# Backplane3_0.net
KiCad netlist of a schematic drawn in Altium Designer
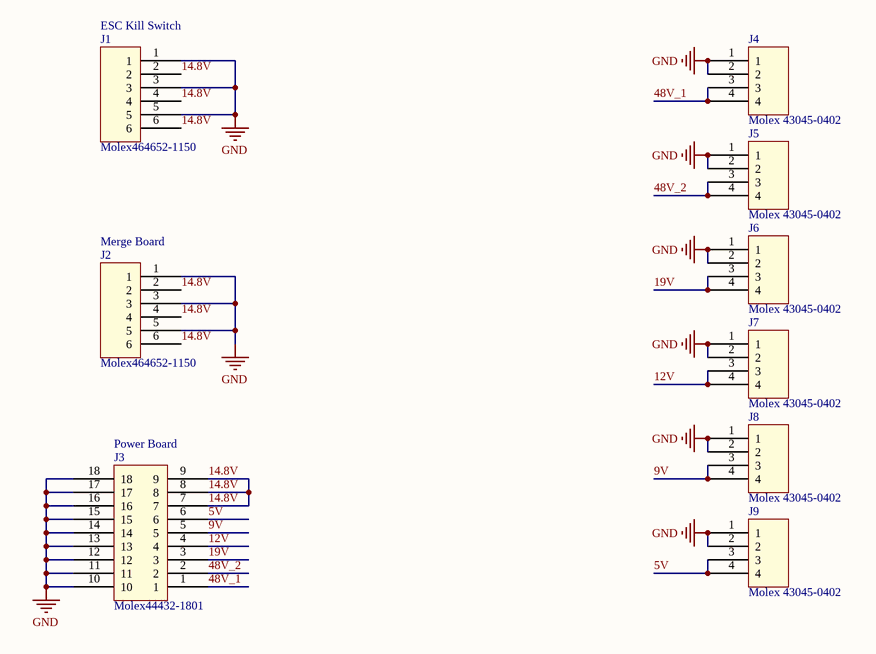
[diagram p0: Backplane3_0.SchDoc]

(export (version "E")
  (design (tool "Eeschema 10.0.6"))
  (components
    (comp (ref "J1")
      (value "Molex464652-1150")
      (footprint "PCBComponent_1")
      (libsource (lib "Molex46562-1150") (part "Molex46562-1150"))
    )
    (comp (ref "J2")
      (value "Molex464652-1150")
      (footprint "PCBComponent_1")
      (libsource (lib "Molex46562-1150") (part "Molex46562-1150"))
    )
    (comp (ref "J3")
      (value "Molex44432-1801")
      (footprint "Molex44432-1801")
      (libsource (lib "Molex44432-1801") (part "Molex44432-1801"))
    )
    (comp (ref "J4")
      (value "Molex 43045-0402")
      (footprint "Molex43045-0402")
      (libsource (lib "Molex43045-0402") (part "Molex43045-0402"))
    )
    (comp (ref "J5")
      (value "Molex 43045-0402")
      (footprint "Molex43045-0402")
      (libsource (lib "Molex43045-0402") (part "Molex43045-0402"))
    )
    (comp (ref "J6")
      (value "Molex 43045-0402")
      (footprint "Molex43045-0402")
      (libsource (lib "Molex43045-0402") (part "Molex43045-0402"))
    )
    (comp (ref "J7")
      (value "Molex 43045-0402")
      (footprint "Molex43045-0402")
      (libsource (lib "Molex43045-0402") (part "Molex43045-0402"))
    )
    (comp (ref "J8")
      (value "Molex 43045-0402")
      (footprint "Molex43045-0402")
      (libsource (lib "Molex43045-0402") (part "Molex43045-0402"))
    )
    (comp (ref "J9")
      (value "Molex 43045-0402")
      (footprint "Molex43045-0402")
      (libsource (lib "Molex43045-0402") (part "Molex43045-0402"))
    )
  )
  (nets
    (net (code "1") (name "/5V") (class "Default")
      (node (ref "J3") (pin "6") (pinfunction "6_6") (pintype "passive"))
      (node (ref "J9") (pin "3") (pinfunction "3_3") (pintype "passive"))
      (node (ref "J9") (pin "4") (pinfunction "4_4") (pintype "passive"))
    )
    (net (code "2") (name "/9V") (class "Default")
      (node (ref "J3") (pin "5") (pinfunction "5_5") (pintype "passive"))
      (node (ref "J8") (pin "3") (pinfunction "3_3") (pintype "passive"))
      (node (ref "J8") (pin "4") (pinfunction "4_4") (pintype "passive"))
    )
    (net (code "3") (name "/12V") (class "Default")
      (node (ref "J3") (pin "4") (pinfunction "4_4") (pintype "passive"))
      (node (ref "J7") (pin "3") (pinfunction "3_3") (pintype "passive"))
      (node (ref "J7") (pin "4") (pinfunction "4_4") (pintype "passive"))
    )
    (net (code "4") (name "/14.8V") (class "Default")
      (node (ref "J1") (pin "2") (pinfunction "2_2") (pintype "passive"))
      (node (ref "J1") (pin "4") (pinfunction "4_4") (pintype "passive"))
      (node (ref "J1") (pin "6") (pinfunction "6_6") (pintype "passive"))
      (node (ref "J2") (pin "2") (pinfunction "2_2") (pintype "passive"))
      (node (ref "J2") (pin "4") (pinfunction "4_4") (pintype "passive"))
      (node (ref "J2") (pin "6") (pinfunction "6_6") (pintype "passive"))
      (node (ref "J3") (pin "7") (pinfunction "7_7") (pintype "passive"))
      (node (ref "J3") (pin "8") (pinfunction "8_8") (pintype "passive"))
      (node (ref "J3") (pin "9") (pinfunction "9_9") (pintype "passive"))
    )
    (net (code "5") (name "/19V") (class "Default")
      (node (ref "J3") (pin "3") (pinfunction "3_3") (pintype "passive"))
      (node (ref "J6") (pin "3") (pinfunction "3_3") (pintype "passive"))
      (node (ref "J6") (pin "4") (pinfunction "4_4") (pintype "passive"))
    )
    (net (code "6") (name "/48V_1") (class "Default")
      (node (ref "J3") (pin "1") (pinfunction "1_1") (pintype "passive"))
      (node (ref "J4") (pin "3") (pinfunction "3_3") (pintype "passive"))
      (node (ref "J4") (pin "4") (pinfunction "4_4") (pintype "passive"))
    )
    (net (code "7") (name "/48V_2") (class "Default")
      (node (ref "J3") (pin "2") (pinfunction "2_2") (pintype "passive"))
      (node (ref "J5") (pin "3") (pinfunction "3_3") (pintype "passive"))
      (node (ref "J5") (pin "4") (pinfunction "4_4") (pintype "passive"))
    )
    (net (code "8") (name "GND") (class "Default")
      (node (ref "J1") (pin "1") (pinfunction "1_1") (pintype "passive"))
      (node (ref "J1") (pin "3") (pinfunction "3_3") (pintype "passive"))
      (node (ref "J1") (pin "5") (pinfunction "5_5") (pintype "passive"))
      (node (ref "J2") (pin "1") (pinfunction "1_1") (pintype "passive"))
      (node (ref "J2") (pin "3") (pinfunction "3_3") (pintype "passive"))
      (node (ref "J2") (pin "5") (pinfunction "5_5") (pintype "passive"))
      (node (ref "J3") (pin "10") (pinfunction "10_10") (pintype "passive"))
      (node (ref "J3") (pin "11") (pinfunction "11_11") (pintype "passive"))
      (node (ref "J3") (pin "12") (pinfunction "12_12") (pintype "passive"))
      (node (ref "J3") (pin "13") (pinfunction "13_13") (pintype "passive"))
      (node (ref "J3") (pin "14") (pinfunction "14_14") (pintype "passive"))
      (node (ref "J3") (pin "15") (pinfunction "15_15") (pintype "passive"))
      (node (ref "J3") (pin "16") (pinfunction "16_16") (pintype "passive"))
      (node (ref "J3") (pin "17") (pinfunction "17_17") (pintype "passive"))
      (node (ref "J3") (pin "18") (pinfunction "18_18") (pintype "passive"))
      (node (ref "J4") (pin "1") (pinfunction "1_1") (pintype "passive"))
      (node (ref "J4") (pin "2") (pinfunction "2_2") (pintype "passive"))
      (node (ref "J5") (pin "1") (pinfunction "1_1") (pintype "passive"))
      (node (ref "J5") (pin "2") (pinfunction "2_2") (pintype "passive"))
      (node (ref "J6") (pin "1") (pinfunction "1_1") (pintype "passive"))
      (node (ref "J6") (pin "2") (pinfunction "2_2") (pintype "passive"))
      (node (ref "J7") (pin "1") (pinfunction "1_1") (pintype "passive"))
      (node (ref "J7") (pin "2") (pinfunction "2_2") (pintype "passive"))
      (node (ref "J8") (pin "1") (pinfunction "1_1") (pintype "passive"))
      (node (ref "J8") (pin "2") (pinfunction "2_2") (pintype "passive"))
      (node (ref "J9") (pin "1") (pinfunction "1_1") (pintype "passive"))
      (node (ref "J9") (pin "2") (pinfunction "2_2") (pintype "passive"))
    )
  )
)
